# driver_pa.net
KiCad netlist of a schematic drawn in EAGLE
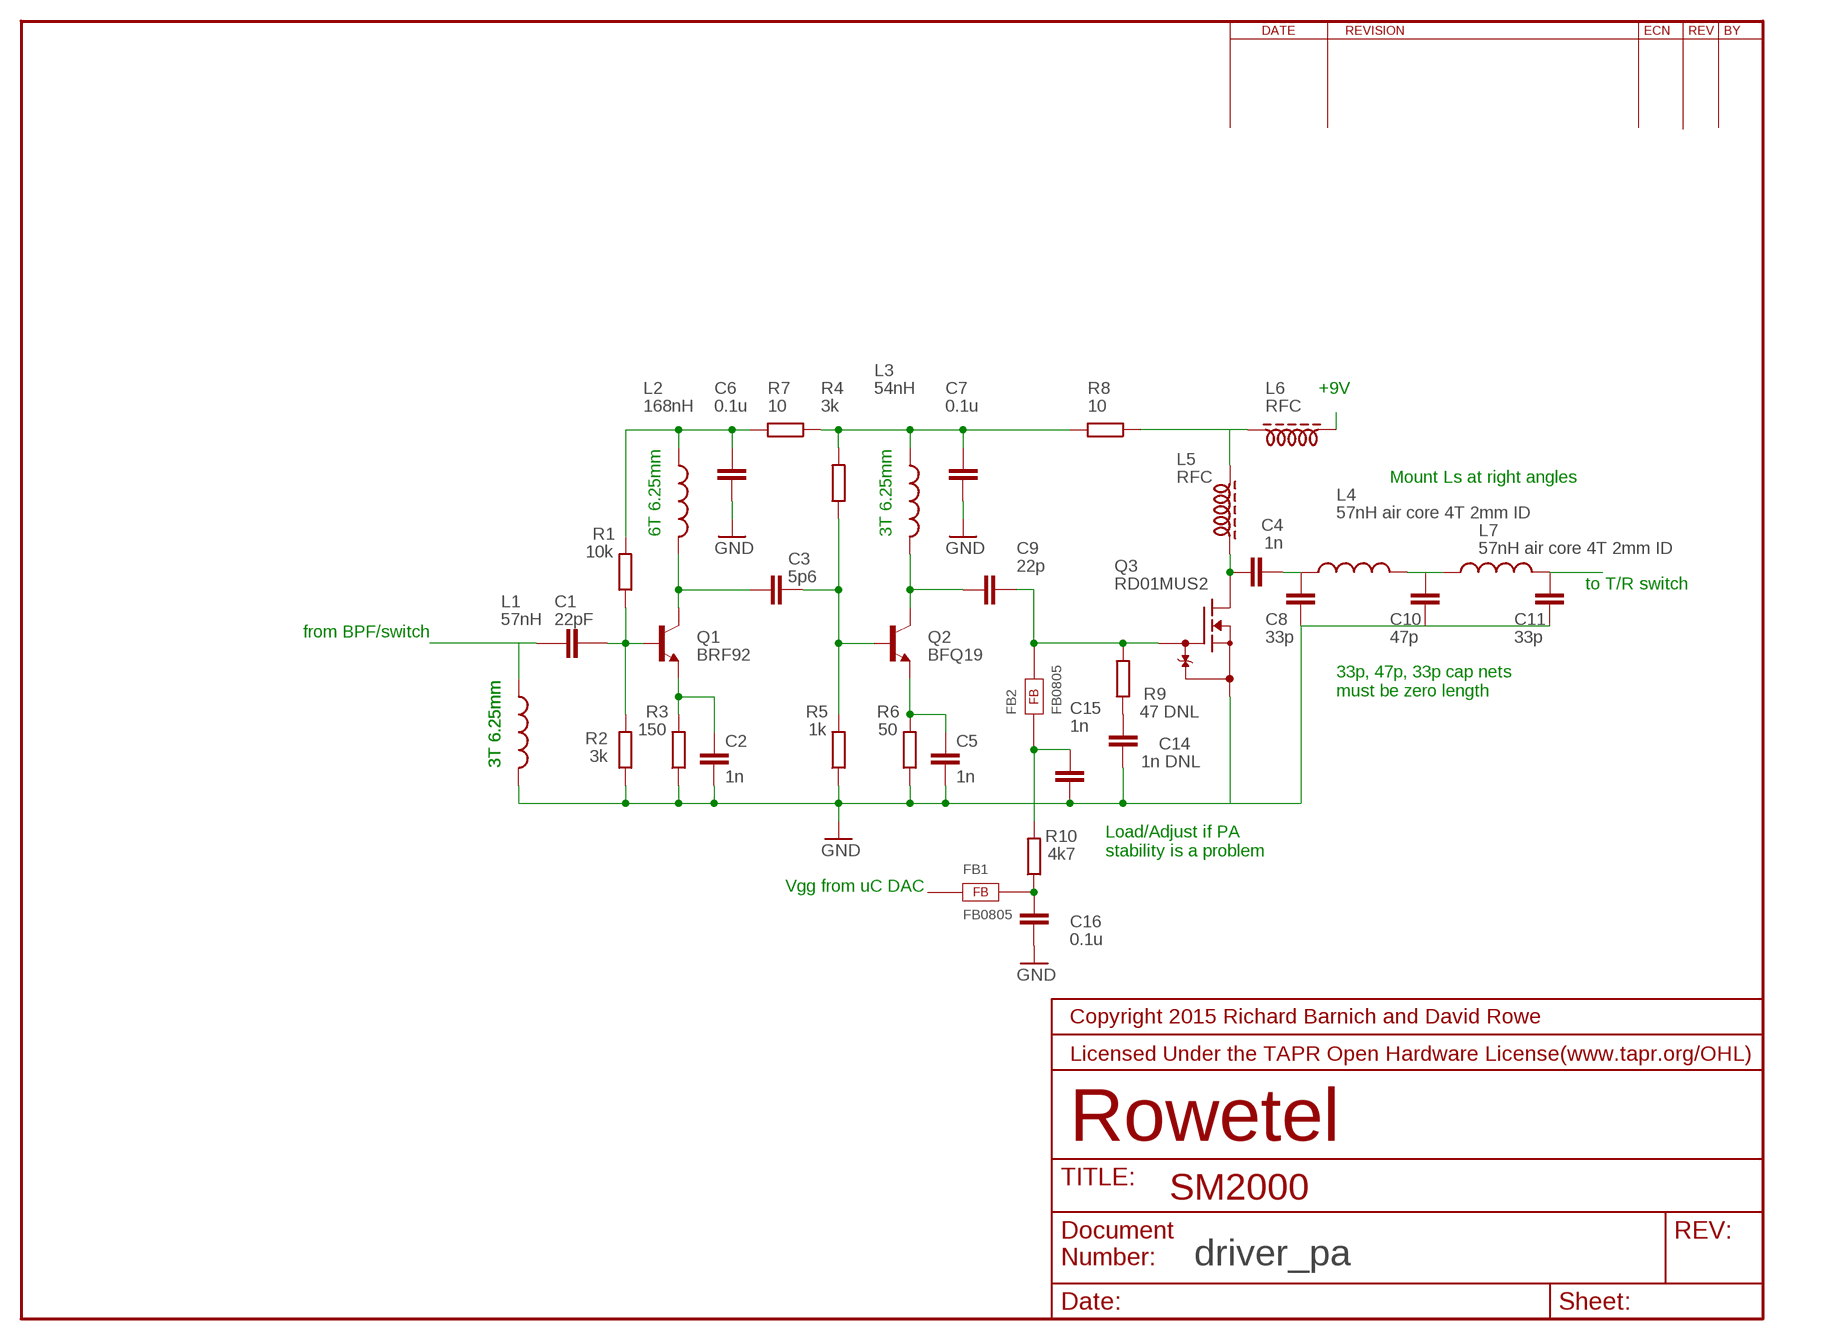
[diagram p0: schematic, sheet 1]

(export (version "E")
  (design (tool "Eeschema 10.0.6"))
  (components
    (comp (ref "C1")
      (value "22pF")
      (footprint "eagle-import:CAPC2012X145AN")
      (libsource (lib "eagle-import") (part "CAPACITOR_0805"))
    )
    (comp (ref "C2")
      (value "1n")
      (footprint "eagle-import:C025-024X044")
      (libsource (lib "eagle-import") (part "C-EU025-024X044"))
    )
    (comp (ref "C3")
      (value "5p6")
      (footprint "eagle-import:C025-024X044")
      (libsource (lib "eagle-import") (part "C-EU025-024X044"))
    )
    (comp (ref "C4")
      (value "1n")
      (footprint "eagle-import:C025-024X044")
      (libsource (lib "eagle-import") (part "C-EU025-024X044"))
    )
    (comp (ref "C5")
      (value "1n")
      (footprint "eagle-import:C025-024X044")
      (libsource (lib "eagle-import") (part "C-EU025-024X044"))
    )
    (comp (ref "C6")
      (value "0.1u")
      (footprint "eagle-import:C025-024X044")
      (libsource (lib "eagle-import") (part "C-EU025-024X044"))
    )
    (comp (ref "C7")
      (value "0.1u")
      (footprint "eagle-import:C025-024X044")
      (libsource (lib "eagle-import") (part "C-EU025-024X044"))
    )
    (comp (ref "C8")
      (value "33p")
      (footprint "eagle-import:C025-024X044")
      (libsource (lib "eagle-import") (part "C-EU025-024X044"))
    )
    (comp (ref "C9")
      (value "22p")
      (footprint "eagle-import:C025-024X044")
      (libsource (lib "eagle-import") (part "C-EU025-024X044"))
    )
    (comp (ref "C10")
      (value "47p")
      (footprint "eagle-import:C025-024X044")
      (libsource (lib "eagle-import") (part "C-EU025-024X044"))
    )
    (comp (ref "C11")
      (value "33p")
      (footprint "eagle-import:C025-024X044")
      (libsource (lib "eagle-import") (part "C-EU025-024X044"))
    )
    (comp (ref "C14")
      (value "1n DNL")
      (footprint "eagle-import:C025-024X044")
      (libsource (lib "eagle-import") (part "C-EU025-024X044"))
    )
    (comp (ref "C15")
      (value "1n")
      (footprint "eagle-import:C025-024X044")
      (libsource (lib "eagle-import") (part "C-EU025-024X044"))
    )
    (comp (ref "C16")
      (value "0.1u")
      (footprint "eagle-import:C025-024X044")
      (libsource (lib "eagle-import") (part "C-EU025-024X044"))
    )
    (comp (ref "FB1")
      (value "FB0805")
      (footprint "eagle-import:FE0805")
      (libsource (lib "eagle-import") (part "FB0805"))
    )
    (comp (ref "FB2")
      (value "FB0805")
      (footprint "eagle-import:FE0805")
      (libsource (lib "eagle-import") (part "FB0805"))
    )
    (comp (ref "L1")
      (value "57nH")
      (footprint "eagle-import:0204_5")
      (libsource (lib "eagle-import") (part "L-US0204/5"))
    )
    (comp (ref "L2")
      (value "168nH")
      (footprint "eagle-import:0204_5")
      (libsource (lib "eagle-import") (part "L-US0204/5"))
    )
    (comp (ref "L3")
      (value "54nH")
      (footprint "eagle-import:0204_5")
      (libsource (lib "eagle-import") (part "L-US0204/5"))
    )
    (comp (ref "L4")
      (value "57nH air core 4T 2mm ID")
      (footprint "eagle-import:0204_5")
      (libsource (lib "eagle-import") (part "L-US0204/5"))
    )
    (comp (ref "L5")
      (value "RFC")
      (footprint "eagle-import:Z15_4")
      (libsource (lib "eagle-import") (part "Z?CCW14/40"))
    )
    (comp (ref "L6")
      (value "RFC")
      (footprint "eagle-import:Z15_4")
      (libsource (lib "eagle-import") (part "Z?CCW14/40"))
    )
    (comp (ref "L7")
      (value "57nH air core 4T 2mm ID")
      (footprint "eagle-import:0204_5")
      (libsource (lib "eagle-import") (part "L-US0204/5"))
    )
    (comp (ref "Q1")
      (value "BRF92")
      (footprint "eagle-import:SOT23-EBC")
      (libsource (lib "eagle-import") (part "-NPN-SOT23-EBC"))
    )
    (comp (ref "Q2")
      (value "BFQ19")
      (footprint "eagle-import:SOT23-EBC")
      (libsource (lib "eagle-import") (part "-NPN-SOT23-EBC"))
    )
    (comp (ref "Q3")
      (value "RD01MUS2")
      (footprint "eagle-import:SOT89")
      (libsource (lib "eagle-import") (part "RD01MUS2"))
    )
    (comp (ref "R1")
      (value "10k")
      (footprint "eagle-import:RESC2012X70N")
      (libsource (lib "eagle-import") (part "RESISTOR_0805"))
    )
    (comp (ref "R2")
      (value "3k")
      (footprint "eagle-import:RESC2012X70N")
      (libsource (lib "eagle-import") (part "RESISTOR_0805"))
    )
    (comp (ref "R3")
      (value "150")
      (footprint "eagle-import:RESC2012X70N")
      (libsource (lib "eagle-import") (part "RESISTOR_0805"))
    )
    (comp (ref "R4")
      (value "3k")
      (footprint "eagle-import:RESC2012X70N")
      (libsource (lib "eagle-import") (part "RESISTOR_0805"))
    )
    (comp (ref "R5")
      (value "1k")
      (footprint "eagle-import:RESC2012X70N")
      (libsource (lib "eagle-import") (part "RESISTOR_0805"))
    )
    (comp (ref "R6")
      (value "50")
      (footprint "eagle-import:RESC2012X70N")
      (libsource (lib "eagle-import") (part "RESISTOR_0805"))
    )
    (comp (ref "R7")
      (value "10")
      (footprint "eagle-import:RESC2012X70N")
      (libsource (lib "eagle-import") (part "RESISTOR_0805"))
    )
    (comp (ref "R8")
      (value "10")
      (footprint "eagle-import:RESC2012X70N")
      (libsource (lib "eagle-import") (part "RESISTOR_0805"))
    )
    (comp (ref "R9")
      (value "47 DNL")
      (footprint "eagle-import:RESC2012X70N")
      (libsource (lib "eagle-import") (part "RESISTOR_0805"))
    )
    (comp (ref "R10")
      (value "4k7")
      (footprint "eagle-import:RESC2012X70N")
      (libsource (lib "eagle-import") (part "RESISTOR_0805"))
    )
  )
  (nets
    (net (code "1") (name "GND") (class "Default")
      (node (ref "C11") (pin "2") (pinfunction "2_2") (pintype "passive"))
      (node (ref "C14") (pin "2") (pinfunction "2_2") (pintype "passive"))
      (node (ref "C15") (pin "2") (pinfunction "2_2") (pintype "passive"))
      (node (ref "C16") (pin "2") (pinfunction "2_2") (pintype "passive"))
      (node (ref "C2") (pin "2") (pinfunction "2_2") (pintype "passive"))
      (node (ref "C5") (pin "2") (pinfunction "2_2") (pintype "passive"))
      (node (ref "C6") (pin "2") (pinfunction "2_2") (pintype "passive"))
      (node (ref "C7") (pin "2") (pinfunction "2_2") (pintype "passive"))
      (node (ref "C8") (pin "2") (pinfunction "2_2") (pintype "passive"))
      (node (ref "L1") (pin "2") (pinfunction "2_2") (pintype "passive"))
      (node (ref "Q3") (pin "2") (pinfunction "S_2") (pintype "passive"))
      (node (ref "Q3") (pin "2.1") (pinfunction "S_2.1") (pintype "passive"))
      (node (ref "R2") (pin "1") (pinfunction "1_1") (pintype "passive"))
      (node (ref "R3") (pin "1") (pinfunction "1_1") (pintype "passive"))
      (node (ref "R5") (pin "1") (pinfunction "1_1") (pintype "passive"))
      (node (ref "R6") (pin "1") (pinfunction "1_1") (pintype "passive"))
    )
    (net (code "2") (name "Net-(C1-Pad1)") (class "Default")
      (node (ref "C1") (pin "1") (pinfunction "1_1") (pintype "passive"))
      (node (ref "Q1") (pin "B") (pinfunction "B_B") (pintype "passive"))
      (node (ref "R1") (pin "1") (pinfunction "1_1") (pintype "passive"))
      (node (ref "R2") (pin "2") (pinfunction "2_2") (pintype "passive"))
    )
    (net (code "3") (name "Net-(C1-Pad2)") (class "Default")
      (node (ref "C1") (pin "2") (pinfunction "2_2") (pintype "passive"))
      (node (ref "L1") (pin "1") (pinfunction "1_1") (pintype "passive"))
    )
    (net (code "4") (name "Net-(C2-Pad1)") (class "Default")
      (node (ref "C2") (pin "1") (pinfunction "1_1") (pintype "passive"))
      (node (ref "Q1") (pin "E") (pinfunction "E_E") (pintype "passive"))
      (node (ref "R3") (pin "2") (pinfunction "2_2") (pintype "passive"))
    )
    (net (code "5") (name "Net-(C3-Pad1)") (class "Default")
      (node (ref "C3") (pin "1") (pinfunction "1_1") (pintype "passive"))
      (node (ref "Q2") (pin "B") (pinfunction "B_B") (pintype "passive"))
      (node (ref "R4") (pin "1") (pinfunction "1_1") (pintype "passive"))
      (node (ref "R5") (pin "2") (pinfunction "2_2") (pintype "passive"))
    )
    (net (code "6") (name "Net-(C3-Pad2)") (class "Default")
      (node (ref "C3") (pin "2") (pinfunction "2_2") (pintype "passive"))
      (node (ref "L2") (pin "2") (pinfunction "2_2") (pintype "passive"))
      (node (ref "Q1") (pin "C") (pinfunction "C_C") (pintype "passive"))
    )
    (net (code "7") (name "Net-(C4-Pad2)") (class "Default")
      (node (ref "C4") (pin "2") (pinfunction "2_2") (pintype "passive"))
      (node (ref "C8") (pin "1") (pinfunction "1_1") (pintype "passive"))
      (node (ref "L4") (pin "1") (pinfunction "1_1") (pintype "passive"))
    )
    (net (code "8") (name "Net-(C5-Pad1)") (class "Default")
      (node (ref "C5") (pin "1") (pinfunction "1_1") (pintype "passive"))
      (node (ref "Q2") (pin "E") (pinfunction "E_E") (pintype "passive"))
      (node (ref "R6") (pin "2") (pinfunction "2_2") (pintype "passive"))
    )
    (net (code "9") (name "Net-(C6-Pad1)") (class "Default")
      (node (ref "C6") (pin "1") (pinfunction "1_1") (pintype "passive"))
      (node (ref "L2") (pin "1") (pinfunction "1_1") (pintype "passive"))
      (node (ref "R1") (pin "2") (pinfunction "2_2") (pintype "passive"))
      (node (ref "R7") (pin "2") (pinfunction "2_2") (pintype "passive"))
    )
    (net (code "10") (name "Net-(C7-Pad1)") (class "Default")
      (node (ref "C7") (pin "1") (pinfunction "1_1") (pintype "passive"))
      (node (ref "L3") (pin "1") (pinfunction "1_1") (pintype "passive"))
      (node (ref "R4") (pin "2") (pinfunction "2_2") (pintype "passive"))
      (node (ref "R7") (pin "1") (pinfunction "1_1") (pintype "passive"))
      (node (ref "R8") (pin "2") (pinfunction "2_2") (pintype "passive"))
    )
    (net (code "11") (name "Net-(C9-Pad2)") (class "Default")
      (node (ref "C9") (pin "2") (pinfunction "2_2") (pintype "passive"))
      (node (ref "L3") (pin "2") (pinfunction "2_2") (pintype "passive"))
      (node (ref "Q2") (pin "C") (pinfunction "C_C") (pintype "passive"))
    )
    (net (code "12") (name "Net-(C10-Pad1)") (class "Default")
      (node (ref "C10") (pin "1") (pinfunction "1_1") (pintype "passive"))
      (node (ref "L4") (pin "2") (pinfunction "2_2") (pintype "passive"))
      (node (ref "L7") (pin "1") (pinfunction "1_1") (pintype "passive"))
    )
    (net (code "13") (name "Net-(C11-Pad1)") (class "Default")
      (node (ref "C11") (pin "1") (pinfunction "1_1") (pintype "passive"))
      (node (ref "L7") (pin "2") (pinfunction "2_2") (pintype "passive"))
    )
    (net (code "14") (name "Net-(C14-Pad1)") (class "Default")
      (node (ref "C14") (pin "1") (pinfunction "1_1") (pintype "passive"))
      (node (ref "R9") (pin "1") (pinfunction "1_1") (pintype "passive"))
    )
    (net (code "15") (name "Net-(C15-Pad1)") (class "Default")
      (node (ref "C15") (pin "1") (pinfunction "1_1") (pintype "passive"))
      (node (ref "FB2") (pin "1") (pinfunction "1_1") (pintype "passive"))
      (node (ref "R10") (pin "2") (pinfunction "2_2") (pintype "passive"))
    )
    (net (code "16") (name "Net-(C16-Pad1)") (class "Default")
      (node (ref "C16") (pin "1") (pinfunction "1_1") (pintype "passive"))
      (node (ref "FB1") (pin "2") (pinfunction "2_2") (pintype "passive"))
      (node (ref "R10") (pin "1") (pinfunction "1_1") (pintype "passive"))
    )
    (net (code "17") (name "Net-(L5-Pad2)") (class "Default")
      (node (ref "L5") (pin "2") (pinfunction "2_2") (pintype "passive"))
      (node (ref "L6") (pin "2") (pinfunction "2_2") (pintype "passive"))
      (node (ref "R8") (pin "1") (pinfunction "1_1") (pintype "passive"))
    )
    (net (code "18") (name "Net-(Q3-D)") (class "Default")
      (node (ref "C4") (pin "1") (pinfunction "1_1") (pintype "passive"))
      (node (ref "L5") (pin "1") (pinfunction "1_1") (pintype "passive"))
      (node (ref "Q3") (pin "3") (pinfunction "D_3") (pintype "passive"))
    )
    (net (code "19") (name "Net-(Q3-G)") (class "Default")
      (node (ref "C9") (pin "1") (pinfunction "1_1") (pintype "passive"))
      (node (ref "FB2") (pin "2") (pinfunction "2_2") (pintype "passive"))
      (node (ref "Q3") (pin "1") (pinfunction "G_1") (pintype "passive"))
      (node (ref "R9") (pin "2") (pinfunction "2_2") (pintype "passive"))
    )
    (net (code "20") (name "unconnected-(C10-Pad2)") (class "Default")
      (node (ref "C10") (pin "2") (pinfunction "2_2") (pintype "passive"))
    )
    (net (code "21") (name "unconnected-(FB1-Pad1)") (class "Default")
      (node (ref "FB1") (pin "1") (pinfunction "1_1") (pintype "passive"))
    )
    (net (code "22") (name "unconnected-(L6-Pad1)") (class "Default")
      (node (ref "L6") (pin "1") (pinfunction "1_1") (pintype "passive"))
    )
  )
)
